# Mako_DSP_Pro_Audio_Codec_R1_0.net
KiCad netlist of a schematic drawn in Altium Designer
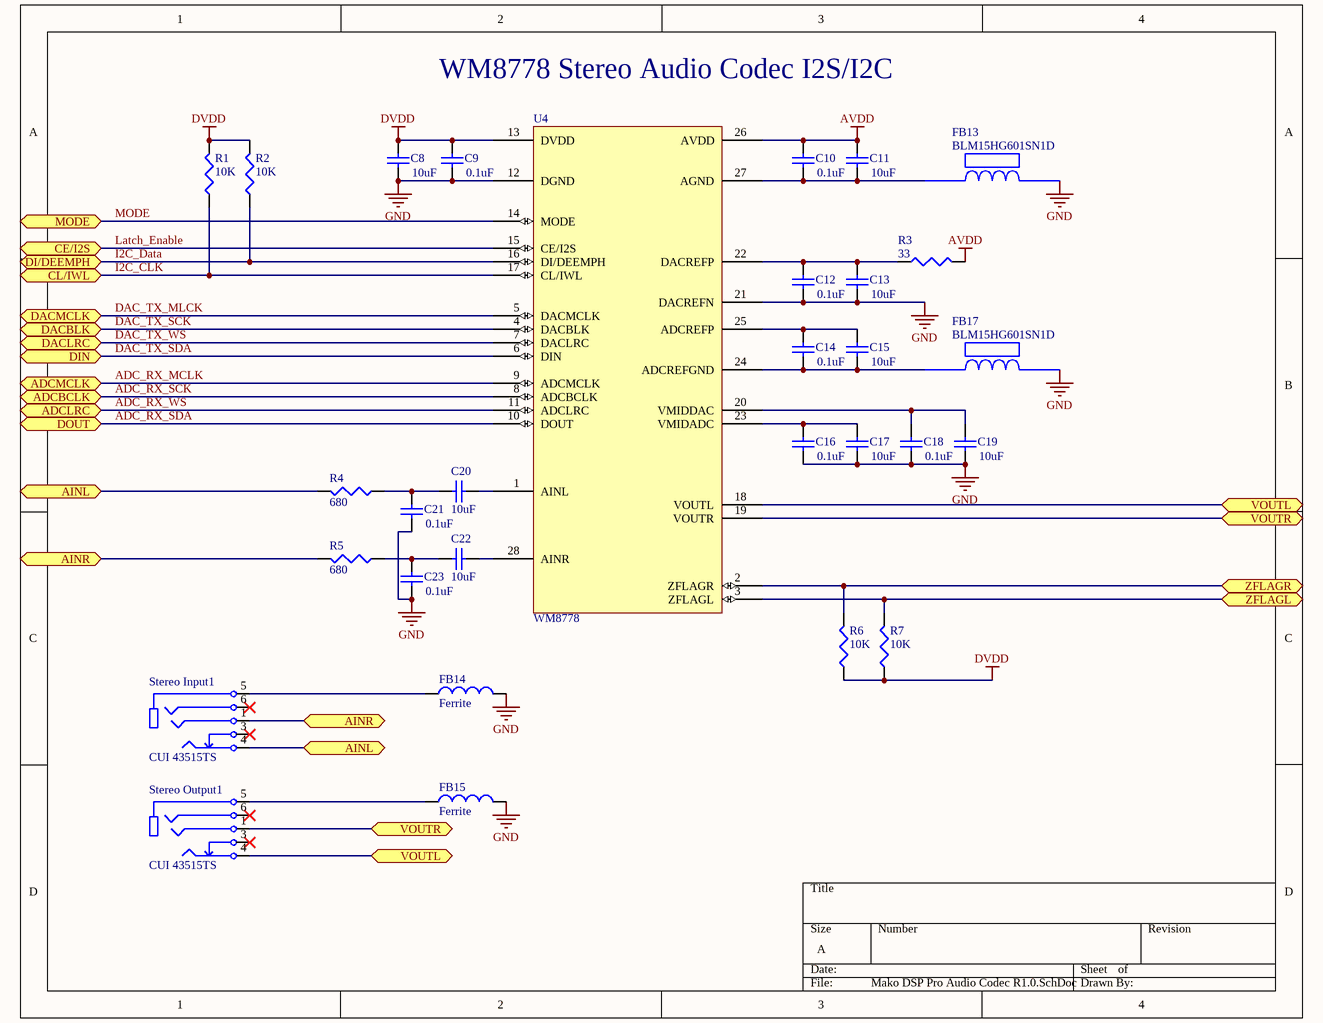
[diagram p0: Mako DSP Pro Audio Codec R1.0.SchDoc]

(export (version "E")
  (design (tool "Eeschema 10.0.6"))
  (components
    (comp (ref "C8")
      (value "10uF")
      (footprint "1608[0603]")
      (description "Capacitor (Semiconductor SIM Model)")
      (fields (field (name "Comment") "Cap Semi") (field (name "PUBLISHER") "Altium Limited"))
      (libsource (lib "Miscellaneous Devices") (part "Cap Semi"))
    )
    (comp (ref "C9")
      (value "0.1uF")
      (footprint "1608[0603]")
      (description "Capacitor (Semiconductor SIM Model)")
      (fields (field (name "Comment") "Cap Semi") (field (name "PUBLISHER") "Altium Limited"))
      (libsource (lib "Miscellaneous Devices") (part "Cap Semi"))
    )
    (comp (ref "C10")
      (value "0.1uF")
      (footprint "1608[0603]")
      (description "Capacitor (Semiconductor SIM Model)")
      (fields (field (name "Comment") "Cap Semi") (field (name "PUBLISHER") "Altium Limited"))
      (libsource (lib "Miscellaneous Devices") (part "Cap Semi"))
    )
    (comp (ref "C11")
      (value "10uF")
      (footprint "1608[0603]")
      (description "Capacitor (Semiconductor SIM Model)")
      (fields (field (name "Comment") "Cap Semi") (field (name "PUBLISHER") "Altium Limited"))
      (libsource (lib "Miscellaneous Devices") (part "Cap Semi"))
    )
    (comp (ref "C12")
      (value "0.1uF")
      (footprint "1608[0603]")
      (description "Capacitor (Semiconductor SIM Model)")
      (fields (field (name "Comment") "Cap Semi") (field (name "PUBLISHER") "Altium Limited"))
      (libsource (lib "Miscellaneous Devices") (part "Cap Semi"))
    )
    (comp (ref "C13")
      (value "10uF")
      (footprint "1608[0603]")
      (description "Capacitor (Semiconductor SIM Model)")
      (fields (field (name "Comment") "Cap Semi") (field (name "PUBLISHER") "Altium Limited"))
      (libsource (lib "Miscellaneous Devices") (part "Cap Semi"))
    )
    (comp (ref "C14")
      (value "0.1uF")
      (footprint "1608[0603]")
      (description "Capacitor (Semiconductor SIM Model)")
      (fields (field (name "Comment") "Cap Semi") (field (name "PUBLISHER") "Altium Limited"))
      (libsource (lib "Miscellaneous Devices") (part "Cap Semi"))
    )
    (comp (ref "C15")
      (value "10uF")
      (footprint "1608[0603]")
      (description "Capacitor (Semiconductor SIM Model)")
      (fields (field (name "Comment") "Cap Semi") (field (name "PUBLISHER") "Altium Limited"))
      (libsource (lib "Miscellaneous Devices") (part "Cap Semi"))
    )
    (comp (ref "C16")
      (value "0.1uF")
      (footprint "1608[0603]")
      (description "Capacitor (Semiconductor SIM Model)")
      (fields (field (name "Comment") "Cap Semi") (field (name "PUBLISHER") "Altium Limited"))
      (libsource (lib "Miscellaneous Devices") (part "Cap Semi"))
    )
    (comp (ref "C17")
      (value "10uF")
      (footprint "1608[0603]")
      (description "Capacitor (Semiconductor SIM Model)")
      (fields (field (name "Comment") "Cap Semi") (field (name "PUBLISHER") "Altium Limited"))
      (libsource (lib "Miscellaneous Devices") (part "Cap Semi"))
    )
    (comp (ref "C18")
      (value "0.1uF")
      (footprint "1608[0603]")
      (description "Capacitor (Semiconductor SIM Model)")
      (fields (field (name "Comment") "Cap Semi") (field (name "PUBLISHER") "Altium Limited"))
      (libsource (lib "Miscellaneous Devices") (part "Cap Semi"))
    )
    (comp (ref "C19")
      (value "10uF")
      (footprint "1608[0603]")
      (description "Capacitor (Semiconductor SIM Model)")
      (fields (field (name "Comment") "Cap Semi") (field (name "PUBLISHER") "Altium Limited"))
      (libsource (lib "Miscellaneous Devices") (part "Cap Semi"))
    )
    (comp (ref "C20")
      (value "10uF")
      (footprint "Panasonic VS B")
      (description "Capacitor (Semiconductor SIM Model)")
      (fields (field (name "Comment") "Cap Semi") (field (name "PUBLISHER") "Altium Limited"))
      (libsource (lib "Miscellaneous Devices") (part "Cap Semi"))
    )
    (comp (ref "C21")
      (value "0.1uF")
      (footprint "SM 0805 - gap trimmed")
      (description "Capacitor (Semiconductor SIM Model)")
      (fields (field (name "Comment") "Cap Semi") (field (name "PUBLISHER") "Altium Limited"))
      (libsource (lib "Miscellaneous Devices") (part "Cap Semi"))
    )
    (comp (ref "C22")
      (value "10uF")
      (footprint "Panasonic VS B")
      (description "Capacitor (Semiconductor SIM Model)")
      (fields (field (name "Comment") "Cap Semi") (field (name "PUBLISHER") "Altium Limited"))
      (libsource (lib "Miscellaneous Devices") (part "Cap Semi"))
    )
    (comp (ref "C23")
      (value "0.1uF")
      (footprint "SM 0805 - gap trimmed")
      (description "Capacitor (Semiconductor SIM Model)")
      (fields (field (name "Comment") "Cap Semi") (field (name "PUBLISHER") "Altium Limited"))
      (libsource (lib "Miscellaneous Devices") (part "Cap Semi"))
    )
    (comp (ref "FB13")
      (value "BLM15HG601SN1D")
      (footprint "BLM18PG121SN1D")
      (libsource (lib "AHD Part Library") (part "BLM15HG601SN1D"))
    )
    (comp (ref "FB14")
      (value "Ferrite")
      (footprint "SM 0805 - gap trimmed")
      (description "Inductor")
      (fields (field (name "PUBLISHER") "Altium Limited"))
      (libsource (lib "Miscellaneous Devices") (part "Inductor"))
    )
    (comp (ref "FB15")
      (value "Ferrite")
      (footprint "SM 0805 - gap trimmed")
      (description "Inductor")
      (fields (field (name "PUBLISHER") "Altium Limited"))
      (libsource (lib "Miscellaneous Devices") (part "Inductor"))
    )
    (comp (ref "FB17")
      (value "BLM15HG601SN1D")
      (footprint "BLM18PG121SN1D")
      (libsource (lib "AHD Part Library") (part "BLM15HG601SN1D"))
    )
    (comp (ref "R1")
      (value "10K")
      (footprint "J1-0603")
      (description "Resistor")
      (fields (field (name "Comment") "Res3") (field (name "PUBLISHER") "Altium Limited"))
      (libsource (lib "Miscellaneous Devices") (part "Res3"))
    )
    (comp (ref "R2")
      (value "10K")
      (footprint "J1-0603")
      (description "Resistor")
      (fields (field (name "Comment") "Res3") (field (name "PUBLISHER") "Altium Limited"))
      (libsource (lib "Miscellaneous Devices") (part "Res3"))
    )
    (comp (ref "R3")
      (value "33")
      (footprint "J1-0603")
      (description "Resistor")
      (fields (field (name "Comment") "Res3") (field (name "PUBLISHER") "Altium Limited"))
      (libsource (lib "Miscellaneous Devices") (part "Res3"))
    )
    (comp (ref "R4")
      (value "680")
      (footprint "SM 0805 - gap trimmed")
      (description "Resistor")
      (fields (field (name "Comment") "Res3") (field (name "PUBLISHER") "Altium Limited"))
      (libsource (lib "Miscellaneous Devices") (part "Res3"))
    )
    (comp (ref "R5")
      (value "680")
      (footprint "SM 0805 - gap trimmed")
      (description "Resistor")
      (fields (field (name "Comment") "Res3") (field (name "PUBLISHER") "Altium Limited"))
      (libsource (lib "Miscellaneous Devices") (part "Res3"))
    )
    (comp (ref "R6")
      (value "10K")
      (footprint "J1-0603")
      (description "Resistor")
      (fields (field (name "Comment") "Res3") (field (name "PUBLISHER") "Altium Limited"))
      (libsource (lib "Miscellaneous Devices") (part "Res3"))
    )
    (comp (ref "R7")
      (value "10K")
      (footprint "J1-0603")
      (description "Resistor")
      (fields (field (name "Comment") "Res3") (field (name "PUBLISHER") "Altium Limited"))
      (libsource (lib "Miscellaneous Devices") (part "Res3"))
    )
    (comp (ref "Stereo Input1")
      (value "CUI 43515TS")
      (footprint "CUI SJ-43515TS")
      (libsource (lib "Adams Altium Library") (part "CUI 43515TS"))
    )
    (comp (ref "Stereo Output1")
      (value "CUI 43515TS")
      (footprint "CUI SJ-43515TS")
      (libsource (lib "Adams Altium Library") (part "CUI 43515TS"))
    )
    (comp (ref "U4")
      (value "WM8778")
      (footprint "WM8778")
      (libsource (lib "Mako DSP Schematic Library") (part "WM8778"))
    )
  )
  (nets
    (net (code "1") (name "/ADC_RX_MCLK") (class "Default")
      (node (ref "U4") (pin "9") (pinfunction "ADCMCLK_9") (pintype "bidirectional"))
    )
    (net (code "2") (name "/ADC_RX_SCK") (class "Default")
      (node (ref "U4") (pin "8") (pinfunction "ADCBCLK_8") (pintype "bidirectional"))
    )
    (net (code "3") (name "/ADC_RX_SDA") (class "Default")
      (node (ref "U4") (pin "10") (pinfunction "DOUT_10") (pintype "bidirectional"))
    )
    (net (code "4") (name "/ADC_RX_WS") (class "Default")
      (node (ref "U4") (pin "11") (pinfunction "ADCLRC_11") (pintype "bidirectional"))
    )
    (net (code "5") (name "/AINL") (class "Default")
      (node (ref "R4") (pin "2") (pinfunction "2_2") (pintype "passive"))
      (node (ref "Stereo Input1") (pin "4") (pinfunction "TIP_4") (pintype "passive"))
    )
    (net (code "6") (name "/AINR") (class "Default")
      (node (ref "R5") (pin "2") (pinfunction "2_2") (pintype "passive"))
      (node (ref "Stereo Input1") (pin "1") (pinfunction "R1_1") (pintype "passive"))
    )
    (net (code "7") (name "/DAC_TX_MLCK") (class "Default")
      (node (ref "U4") (pin "5") (pinfunction "DACMCLK_5") (pintype "bidirectional"))
    )
    (net (code "8") (name "/DAC_TX_SCK") (class "Default")
      (node (ref "U4") (pin "4") (pinfunction "DACBLK_4") (pintype "bidirectional"))
    )
    (net (code "9") (name "/DAC_TX_SDA") (class "Default")
      (node (ref "U4") (pin "6") (pinfunction "DIN_6") (pintype "bidirectional"))
    )
    (net (code "10") (name "/DAC_TX_WS") (class "Default")
      (node (ref "U4") (pin "7") (pinfunction "DACLRC_7") (pintype "bidirectional"))
    )
    (net (code "11") (name "/I2C_CLK") (class "Default")
      (node (ref "R1") (pin "1") (pinfunction "1_1") (pintype "passive"))
      (node (ref "U4") (pin "17") (pinfunction "CL/IWL_17") (pintype "bidirectional"))
    )
    (net (code "12") (name "/I2C_Data") (class "Default")
      (node (ref "R2") (pin "1") (pinfunction "1_1") (pintype "passive"))
      (node (ref "U4") (pin "16") (pinfunction "DI/DEEMPH_16") (pintype "bidirectional"))
    )
    (net (code "13") (name "/Latch_Enable") (class "Default")
      (node (ref "U4") (pin "15") (pinfunction "CE/I2S_15") (pintype "bidirectional"))
    )
    (net (code "14") (name "/MODE") (class "Default")
      (node (ref "U4") (pin "14") (pinfunction "MODE_14") (pintype "bidirectional"))
    )
    (net (code "15") (name "/VOUTL") (class "Default")
      (node (ref "Stereo Output1") (pin "4") (pinfunction "TIP_4") (pintype "passive"))
      (node (ref "U4") (pin "18") (pinfunction "VOUTL_18") (pintype "passive"))
    )
    (net (code "16") (name "/VOUTR") (class "Default")
      (node (ref "Stereo Output1") (pin "1") (pinfunction "R1_1") (pintype "passive"))
      (node (ref "U4") (pin "19") (pinfunction "VOUTR_19") (pintype "passive"))
    )
    (net (code "17") (name "/ZFLAGL") (class "Default")
      (node (ref "R7") (pin "2") (pinfunction "2_2") (pintype "passive"))
      (node (ref "U4") (pin "3") (pinfunction "ZFLAGL_3") (pintype "bidirectional"))
    )
    (net (code "18") (name "/ZFLAGR") (class "Default")
      (node (ref "R6") (pin "2") (pinfunction "2_2") (pintype "passive"))
      (node (ref "U4") (pin "2") (pinfunction "ZFLAGR_2") (pintype "bidirectional"))
    )
    (net (code "19") (name "AVDD") (class "Default")
      (node (ref "C10") (pin "2") (pinfunction "2_2") (pintype "passive"))
      (node (ref "C11") (pin "2") (pinfunction "2_2") (pintype "passive"))
      (node (ref "R3") (pin "2") (pinfunction "2_2") (pintype "passive"))
      (node (ref "U4") (pin "26") (pinfunction "AVDD_26") (pintype "passive"))
    )
    (net (code "20") (name "DVDD") (class "Default")
      (node (ref "C8") (pin "2") (pinfunction "2_2") (pintype "passive"))
      (node (ref "C9") (pin "2") (pinfunction "2_2") (pintype "passive"))
      (node (ref "R1") (pin "2") (pinfunction "2_2") (pintype "passive"))
      (node (ref "R2") (pin "2") (pinfunction "2_2") (pintype "passive"))
      (node (ref "R6") (pin "1") (pinfunction "1_1") (pintype "passive"))
      (node (ref "R7") (pin "1") (pinfunction "1_1") (pintype "passive"))
      (node (ref "U4") (pin "13") (pinfunction "DVDD_13") (pintype "passive"))
    )
    (net (code "21") (name "GND") (class "Default")
      (node (ref "C12") (pin "1") (pinfunction "1_1") (pintype "passive"))
      (node (ref "C13") (pin "1") (pinfunction "1_1") (pintype "passive"))
      (node (ref "C16") (pin "1") (pinfunction "1_1") (pintype "passive"))
      (node (ref "C17") (pin "1") (pinfunction "1_1") (pintype "passive"))
      (node (ref "C18") (pin "1") (pinfunction "1_1") (pintype "passive"))
      (node (ref "C19") (pin "1") (pinfunction "1_1") (pintype "passive"))
      (node (ref "C21") (pin "1") (pinfunction "1_1") (pintype "passive"))
      (node (ref "C23") (pin "1") (pinfunction "1_1") (pintype "passive"))
      (node (ref "C8") (pin "1") (pinfunction "1_1") (pintype "passive"))
      (node (ref "C9") (pin "1") (pinfunction "1_1") (pintype "passive"))
      (node (ref "FB13") (pin "2") (pinfunction "2_2") (pintype "passive"))
      (node (ref "FB14") (pin "2") (pinfunction "2_2") (pintype "passive"))
      (node (ref "FB15") (pin "2") (pinfunction "2_2") (pintype "passive"))
      (node (ref "FB17") (pin "2") (pinfunction "2_2") (pintype "passive"))
      (node (ref "U4") (pin "12") (pinfunction "DGND_12") (pintype "passive"))
      (node (ref "U4") (pin "21") (pinfunction "DACREFN_21") (pintype "passive"))
    )
    (net (code "22") (name "Net-(C20-Pad2)") (class "Default")
      (node (ref "C20") (pin "2") (pinfunction "2_2") (pintype "passive"))
      (node (ref "C21") (pin "2") (pinfunction "2_2") (pintype "passive"))
      (node (ref "R4") (pin "1") (pinfunction "1_1") (pintype "passive"))
    )
    (net (code "23") (name "Net-(C22-Pad2)") (class "Default")
      (node (ref "C22") (pin "2") (pinfunction "2_2") (pintype "passive"))
      (node (ref "C23") (pin "2") (pinfunction "2_2") (pintype "passive"))
      (node (ref "R5") (pin "1") (pinfunction "1_1") (pintype "passive"))
    )
    (net (code "24") (name "Net-(Stereo Input1-SLEEVE)") (class "Default")
      (node (ref "FB14") (pin "1") (pinfunction "1_1") (pintype "passive"))
      (node (ref "Stereo Input1") (pin "5") (pinfunction "SLEEVE_5") (pintype "passive"))
    )
    (net (code "25") (name "Net-(Stereo Output1-SLEEVE)") (class "Default")
      (node (ref "FB15") (pin "1") (pinfunction "1_1") (pintype "passive"))
      (node (ref "Stereo Output1") (pin "5") (pinfunction "SLEEVE_5") (pintype "passive"))
    )
    (net (code "26") (name "Net-(U4-ADCREFGND)") (class "Default")
      (node (ref "C14") (pin "1") (pinfunction "1_1") (pintype "passive"))
      (node (ref "C15") (pin "1") (pinfunction "1_1") (pintype "passive"))
      (node (ref "FB17") (pin "1") (pinfunction "1_1") (pintype "passive"))
      (node (ref "U4") (pin "24") (pinfunction "ADCREFGND_24") (pintype "passive"))
    )
    (net (code "27") (name "Net-(U4-ADCREFP)") (class "Default")
      (node (ref "C14") (pin "2") (pinfunction "2_2") (pintype "passive"))
      (node (ref "C15") (pin "2") (pinfunction "2_2") (pintype "passive"))
      (node (ref "U4") (pin "25") (pinfunction "ADCREFP_25") (pintype "passive"))
    )
    (net (code "28") (name "Net-(U4-AGND)") (class "Default")
      (node (ref "C10") (pin "1") (pinfunction "1_1") (pintype "passive"))
      (node (ref "C11") (pin "1") (pinfunction "1_1") (pintype "passive"))
      (node (ref "FB13") (pin "1") (pinfunction "1_1") (pintype "passive"))
      (node (ref "U4") (pin "27") (pinfunction "AGND_27") (pintype "passive"))
    )
    (net (code "29") (name "Net-(U4-AINL)") (class "Default")
      (node (ref "C20") (pin "1") (pinfunction "1_1") (pintype "passive"))
      (node (ref "U4") (pin "1") (pinfunction "AINL_1") (pintype "passive"))
    )
    (net (code "30") (name "Net-(U4-AINR)") (class "Default")
      (node (ref "C22") (pin "1") (pinfunction "1_1") (pintype "passive"))
      (node (ref "U4") (pin "28") (pinfunction "AINR_28") (pintype "passive"))
    )
    (net (code "31") (name "Net-(U4-DACREFP)") (class "Default")
      (node (ref "C12") (pin "2") (pinfunction "2_2") (pintype "passive"))
      (node (ref "C13") (pin "2") (pinfunction "2_2") (pintype "passive"))
      (node (ref "R3") (pin "1") (pinfunction "1_1") (pintype "passive"))
      (node (ref "U4") (pin "22") (pinfunction "DACREFP_22") (pintype "passive"))
    )
    (net (code "32") (name "Net-(U4-VMIDADC)") (class "Default")
      (node (ref "C16") (pin "2") (pinfunction "2_2") (pintype "passive"))
      (node (ref "C17") (pin "2") (pinfunction "2_2") (pintype "passive"))
      (node (ref "U4") (pin "23") (pinfunction "VMIDADC_23") (pintype "passive"))
    )
    (net (code "33") (name "Net-(U4-VMIDDAC)") (class "Default")
      (node (ref "C18") (pin "2") (pinfunction "2_2") (pintype "passive"))
      (node (ref "C19") (pin "2") (pinfunction "2_2") (pintype "passive"))
      (node (ref "U4") (pin "20") (pinfunction "VMIDDAC_20") (pintype "passive"))
    )
    (net (code "34") (name "unconnected-(Stereo Input1-R2-Pad6)") (class "Default")
      (node (ref "Stereo Input1") (pin "6") (pinfunction "R2_6") (pintype "passive+no_connect"))
    )
    (net (code "35") (name "unconnected-(Stereo Input1-TS-Pad3)") (class "Default")
      (node (ref "Stereo Input1") (pin "3") (pinfunction "TS_3") (pintype "passive+no_connect"))
    )
    (net (code "36") (name "unconnected-(Stereo Output1-R2-Pad6)") (class "Default")
      (node (ref "Stereo Output1") (pin "6") (pinfunction "R2_6") (pintype "passive+no_connect"))
    )
    (net (code "37") (name "unconnected-(Stereo Output1-TS-Pad3)") (class "Default")
      (node (ref "Stereo Output1") (pin "3") (pinfunction "TS_3") (pintype "passive+no_connect"))
    )
  )
)
